# BackplaneConnector.net
KiCad netlist of a schematic drawn in Altium Designer
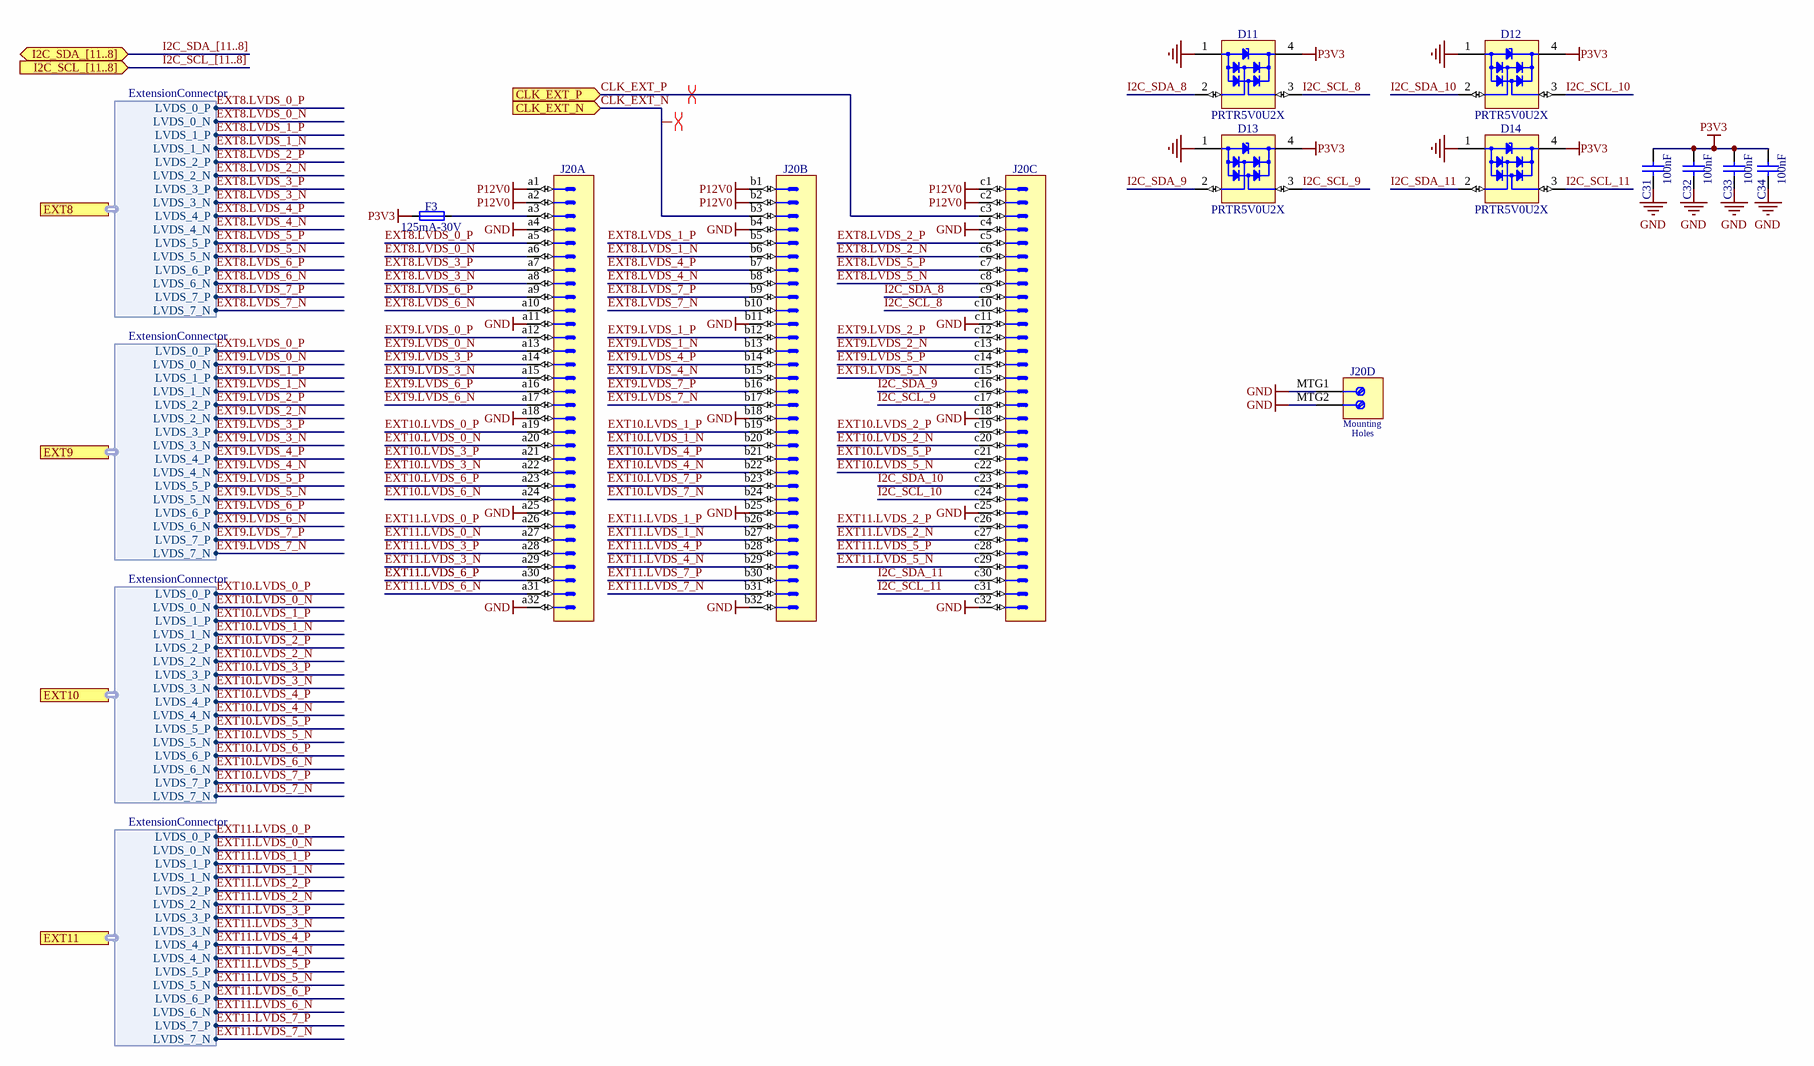
[diagram p0: BackplaneConnector.SchDoc]

(export (version "E")
  (design (tool "Eeschema 10.0.6"))
  (components
    (comp (ref "C31")
      (value "100nF")
      (footprint "CAPC0603X33N")
      (description "Non-polarised capacitor")
      (fields
        (field (name "PART NUMBER") "CC0201_100NF_6.3V_10%_X5R")
        (field (name "VOLTAGE") "6.3V")
        (field (name "AUTHOR") "CERN DEM JLC")
      )
      (libsource (lib "Capacitors") (part "Capacitor - non polarized"))
    )
    (comp (ref "C32")
      (value "100nF")
      (footprint "CAPC0603X33N")
      (description "Non-polarised capacitor")
      (fields
        (field (name "PART NUMBER") "CC0201_100NF_6.3V_10%_X5R")
        (field (name "VOLTAGE") "6.3V")
        (field (name "AUTHOR") "CERN DEM JLC")
      )
      (libsource (lib "Capacitors") (part "Capacitor - non polarized"))
    )
    (comp (ref "C33")
      (value "100nF")
      (footprint "CAPC0603X33N")
      (description "Non-polarised capacitor")
      (fields
        (field (name "PART NUMBER") "CC0201_100NF_6.3V_10%_X5R")
        (field (name "VOLTAGE") "6.3V")
        (field (name "AUTHOR") "CERN DEM JLC")
      )
      (libsource (lib "Capacitors") (part "Capacitor - non polarized"))
    )
    (comp (ref "C34")
      (value "100nF")
      (footprint "CAPC0603X33N")
      (description "Non-polarised capacitor")
      (fields
        (field (name "PART NUMBER") "CC0201_100NF_6.3V_10%_X5R")
        (field (name "VOLTAGE") "6.3V")
        (field (name "AUTHOR") "CERN DEM JLC")
      )
      (libsource (lib "Capacitors") (part "Capacitor - non polarized"))
    )
    (comp (ref "D11")
      (value "PRTR5V0U2X")
      (footprint "SOT190P230X110-4N")
      (description "Ultra Low Capacitance Double Rail-to-Rail ESD Protection Diode")
      (fields
        (field (name "VOLTAGE") "5.5V")
        (field (name "MANUFACTURER") "NXP SEMICONDUCTORS")
        (field (name "AUTHOR") "CERN DEM JLC")
      )
      (libsource (lib "ICs And Semiconductors") (part "PRTR5V0U2X"))
    )
    (comp (ref "D12")
      (value "PRTR5V0U2X")
      (footprint "SOT190P230X110-4N")
      (description "Ultra Low Capacitance Double Rail-to-Rail ESD Protection Diode")
      (fields
        (field (name "VOLTAGE") "5.5V")
        (field (name "MANUFACTURER") "NXP SEMICONDUCTORS")
        (field (name "AUTHOR") "CERN DEM JLC")
      )
      (libsource (lib "ICs And Semiconductors") (part "PRTR5V0U2X"))
    )
    (comp (ref "D13")
      (value "PRTR5V0U2X")
      (footprint "SOT190P230X110-4N")
      (description "Ultra Low Capacitance Double Rail-to-Rail ESD Protection Diode")
      (fields
        (field (name "VOLTAGE") "5.5V")
        (field (name "MANUFACTURER") "NXP SEMICONDUCTORS")
        (field (name "AUTHOR") "CERN DEM JLC")
      )
      (libsource (lib "ICs And Semiconductors") (part "PRTR5V0U2X"))
    )
    (comp (ref "D14")
      (value "PRTR5V0U2X")
      (footprint "SOT190P230X110-4N")
      (description "Ultra Low Capacitance Double Rail-to-Rail ESD Protection Diode")
      (fields
        (field (name "VOLTAGE") "5.5V")
        (field (name "MANUFACTURER") "NXP SEMICONDUCTORS")
        (field (name "AUTHOR") "CERN DEM JLC")
      )
      (libsource (lib "ICs And Semiconductors") (part "PRTR5V0U2X"))
    )
    (comp (ref "F3")
      (value "125mA-30V")
      (footprint "FUSR_LITTELFUSE_1206L012")
      (description "Fuse")
      (fields
        (field (name "PART NUMBER") "FUSR_LITTELFUSE_1206L012")
        (field (name "MANUFACTURER") "LITTELFUSE")
        (field (name "AUTHOR") "CERN DEM JLC")
      )
      (libsource (lib "Eletro-mechanical") (part "Fuse"))
    )
    (comp (ref "J20")
      (value "DIN 41612 Type C")
      (footprint "HARTING_09 03 196 2921")
      (description "Connector 96abc male (3x32)")
      (fields
        (field (name "PART NUMBER") "HARTING_09 03 196 2921")
        (field (name "MANUFACTURER") "HARTING")
        (field (name "AUTHOR") "CERN DEM JLC")
      )
      (libsource (lib "Connectors") (part "Connector 96abc male (3x32)"))
    )
  )
  (nets
    (net (code "2") (name "/CLK_EXT_N") (class "Default")
      (node (ref "J20") (pin "b3") (pinfunction "b3_b3") (pintype "bidirectional"))
    )
    (net (code "3") (name "/CLK_EXT_P") (class "Default")
      (node (ref "J20") (pin "c3") (pinfunction "c3_c3") (pintype "bidirectional"))
    )
    (net (code "4") (name "/EXT8.LVDS_0_N") (class "Default")
      (node (ref "J20") (pin "a6") (pinfunction "a6_a6") (pintype "bidirectional"))
    )
    (net (code "5") (name "/EXT8.LVDS_0_P") (class "Default")
      (node (ref "J20") (pin "a5") (pinfunction "a5_a5") (pintype "bidirectional"))
    )
    (net (code "6") (name "/EXT8.LVDS_1_N") (class "Default")
      (node (ref "J20") (pin "b6") (pinfunction "b6_b6") (pintype "bidirectional"))
    )
    (net (code "7") (name "/EXT8.LVDS_1_P") (class "Default")
      (node (ref "J20") (pin "b5") (pinfunction "b5_b5") (pintype "bidirectional"))
    )
    (net (code "8") (name "/EXT8.LVDS_2_N") (class "Default")
      (node (ref "J20") (pin "c6") (pinfunction "c6_c6") (pintype "bidirectional"))
    )
    (net (code "9") (name "/EXT8.LVDS_2_P") (class "Default")
      (node (ref "J20") (pin "c5") (pinfunction "c5_c5") (pintype "bidirectional"))
    )
    (net (code "10") (name "/EXT8.LVDS_3_N") (class "Default")
      (node (ref "J20") (pin "a8") (pinfunction "a8_a8") (pintype "bidirectional"))
    )
    (net (code "11") (name "/EXT8.LVDS_3_P") (class "Default")
      (node (ref "J20") (pin "a7") (pinfunction "a7_a7") (pintype "bidirectional"))
    )
    (net (code "12") (name "/EXT8.LVDS_4_N") (class "Default")
      (node (ref "J20") (pin "b8") (pinfunction "b8_b8") (pintype "bidirectional"))
    )
    (net (code "13") (name "/EXT8.LVDS_4_P") (class "Default")
      (node (ref "J20") (pin "b7") (pinfunction "b7_b7") (pintype "bidirectional"))
    )
    (net (code "14") (name "/EXT8.LVDS_5_N") (class "Default")
      (node (ref "J20") (pin "c8") (pinfunction "c8_c8") (pintype "bidirectional"))
    )
    (net (code "15") (name "/EXT8.LVDS_5_P") (class "Default")
      (node (ref "J20") (pin "c7") (pinfunction "c7_c7") (pintype "bidirectional"))
    )
    (net (code "16") (name "/EXT8.LVDS_6_N") (class "Default")
      (node (ref "J20") (pin "a10") (pinfunction "a10_a10") (pintype "bidirectional"))
    )
    (net (code "17") (name "/EXT8.LVDS_6_P") (class "Default")
      (node (ref "J20") (pin "a9") (pinfunction "a9_a9") (pintype "bidirectional"))
    )
    (net (code "18") (name "/EXT8.LVDS_7_N") (class "Default")
      (node (ref "J20") (pin "b10") (pinfunction "b10_b10") (pintype "bidirectional"))
    )
    (net (code "19") (name "/EXT8.LVDS_7_P") (class "Default")
      (node (ref "J20") (pin "b9") (pinfunction "b9_b9") (pintype "bidirectional"))
    )
    (net (code "20") (name "/EXT9.LVDS_0_N") (class "Default")
      (node (ref "J20") (pin "a13") (pinfunction "a13_a13") (pintype "bidirectional"))
    )
    (net (code "21") (name "/EXT9.LVDS_0_P") (class "Default")
      (node (ref "J20") (pin "a12") (pinfunction "a12_a12") (pintype "bidirectional"))
    )
    (net (code "22") (name "/EXT9.LVDS_1_N") (class "Default")
      (node (ref "J20") (pin "b13") (pinfunction "b13_b13") (pintype "bidirectional"))
    )
    (net (code "23") (name "/EXT9.LVDS_1_P") (class "Default")
      (node (ref "J20") (pin "b12") (pinfunction "b12_b12") (pintype "bidirectional"))
    )
    (net (code "24") (name "/EXT9.LVDS_2_N") (class "Default")
      (node (ref "J20") (pin "c13") (pinfunction "c13_c13") (pintype "bidirectional"))
    )
    (net (code "25") (name "/EXT9.LVDS_2_P") (class "Default")
      (node (ref "J20") (pin "c12") (pinfunction "c12_c12") (pintype "bidirectional"))
    )
    (net (code "26") (name "/EXT9.LVDS_3_N") (class "Default")
      (node (ref "J20") (pin "a15") (pinfunction "a15_a15") (pintype "bidirectional"))
    )
    (net (code "27") (name "/EXT9.LVDS_3_P") (class "Default")
      (node (ref "J20") (pin "a14") (pinfunction "a14_a14") (pintype "bidirectional"))
    )
    (net (code "28") (name "/EXT9.LVDS_4_N") (class "Default")
      (node (ref "J20") (pin "b15") (pinfunction "b15_b15") (pintype "bidirectional"))
    )
    (net (code "29") (name "/EXT9.LVDS_4_P") (class "Default")
      (node (ref "J20") (pin "b14") (pinfunction "b14_b14") (pintype "bidirectional"))
    )
    (net (code "30") (name "/EXT9.LVDS_5_N") (class "Default")
      (node (ref "J20") (pin "c15") (pinfunction "c15_c15") (pintype "bidirectional"))
    )
    (net (code "31") (name "/EXT9.LVDS_5_P") (class "Default")
      (node (ref "J20") (pin "c14") (pinfunction "c14_c14") (pintype "bidirectional"))
    )
    (net (code "32") (name "/EXT9.LVDS_6_N") (class "Default")
      (node (ref "J20") (pin "a17") (pinfunction "a17_a17") (pintype "bidirectional"))
    )
    (net (code "33") (name "/EXT9.LVDS_6_P") (class "Default")
      (node (ref "J20") (pin "a16") (pinfunction "a16_a16") (pintype "bidirectional"))
    )
    (net (code "34") (name "/EXT9.LVDS_7_N") (class "Default")
      (node (ref "J20") (pin "b17") (pinfunction "b17_b17") (pintype "bidirectional"))
    )
    (net (code "35") (name "/EXT9.LVDS_7_P") (class "Default")
      (node (ref "J20") (pin "b16") (pinfunction "b16_b16") (pintype "bidirectional"))
    )
    (net (code "36") (name "/EXT10.LVDS_0_N") (class "Default")
      (node (ref "J20") (pin "a20") (pinfunction "a20_a20") (pintype "bidirectional"))
    )
    (net (code "37") (name "/EXT10.LVDS_0_P") (class "Default")
      (node (ref "J20") (pin "a19") (pinfunction "a19_a19") (pintype "bidirectional"))
    )
    (net (code "38") (name "/EXT10.LVDS_1_N") (class "Default")
      (node (ref "J20") (pin "b20") (pinfunction "b20_b20") (pintype "bidirectional"))
    )
    (net (code "39") (name "/EXT10.LVDS_1_P") (class "Default")
      (node (ref "J20") (pin "b19") (pinfunction "b19_b19") (pintype "bidirectional"))
    )
    (net (code "40") (name "/EXT10.LVDS_2_N") (class "Default")
      (node (ref "J20") (pin "c20") (pinfunction "c20_c20") (pintype "bidirectional"))
    )
    (net (code "41") (name "/EXT10.LVDS_2_P") (class "Default")
      (node (ref "J20") (pin "c19") (pinfunction "c19_c19") (pintype "bidirectional"))
    )
    (net (code "42") (name "/EXT10.LVDS_3_N") (class "Default")
      (node (ref "J20") (pin "a22") (pinfunction "a22_a22") (pintype "bidirectional"))
    )
    (net (code "43") (name "/EXT10.LVDS_3_P") (class "Default")
      (node (ref "J20") (pin "a21") (pinfunction "a21_a21") (pintype "bidirectional"))
    )
    (net (code "44") (name "/EXT10.LVDS_4_N") (class "Default")
      (node (ref "J20") (pin "b22") (pinfunction "b22_b22") (pintype "bidirectional"))
    )
    (net (code "45") (name "/EXT10.LVDS_4_P") (class "Default")
      (node (ref "J20") (pin "b21") (pinfunction "b21_b21") (pintype "bidirectional"))
    )
    (net (code "46") (name "/EXT10.LVDS_5_N") (class "Default")
      (node (ref "J20") (pin "c22") (pinfunction "c22_c22") (pintype "bidirectional"))
    )
    (net (code "47") (name "/EXT10.LVDS_5_P") (class "Default")
      (node (ref "J20") (pin "c21") (pinfunction "c21_c21") (pintype "bidirectional"))
    )
    (net (code "48") (name "/EXT10.LVDS_6_N") (class "Default")
      (node (ref "J20") (pin "a24") (pinfunction "a24_a24") (pintype "bidirectional"))
    )
    (net (code "49") (name "/EXT10.LVDS_6_P") (class "Default")
      (node (ref "J20") (pin "a23") (pinfunction "a23_a23") (pintype "bidirectional"))
    )
    (net (code "50") (name "/EXT10.LVDS_7_N") (class "Default")
      (node (ref "J20") (pin "b24") (pinfunction "b24_b24") (pintype "bidirectional"))
    )
    (net (code "51") (name "/EXT10.LVDS_7_P") (class "Default")
      (node (ref "J20") (pin "b23") (pinfunction "b23_b23") (pintype "bidirectional"))
    )
    (net (code "52") (name "/EXT11.LVDS_0_N") (class "Default")
      (node (ref "J20") (pin "a27") (pinfunction "a27_a27") (pintype "bidirectional"))
    )
    (net (code "53") (name "/EXT11.LVDS_0_P") (class "Default")
      (node (ref "J20") (pin "a26") (pinfunction "a26_a26") (pintype "bidirectional"))
    )
    (net (code "54") (name "/EXT11.LVDS_1_N") (class "Default")
      (node (ref "J20") (pin "b27") (pinfunction "b27_b27") (pintype "bidirectional"))
    )
    (net (code "55") (name "/EXT11.LVDS_1_P") (class "Default")
      (node (ref "J20") (pin "b26") (pinfunction "b26_b26") (pintype "bidirectional"))
    )
    (net (code "56") (name "/EXT11.LVDS_2_N") (class "Default")
      (node (ref "J20") (pin "c27") (pinfunction "c27_c27") (pintype "bidirectional"))
    )
    (net (code "57") (name "/EXT11.LVDS_2_P") (class "Default")
      (node (ref "J20") (pin "c26") (pinfunction "c26_c26") (pintype "bidirectional"))
    )
    (net (code "58") (name "/EXT11.LVDS_3_N") (class "Default")
      (node (ref "J20") (pin "a29") (pinfunction "a29_a29") (pintype "bidirectional"))
    )
    (net (code "59") (name "/EXT11.LVDS_3_P") (class "Default")
      (node (ref "J20") (pin "a28") (pinfunction "a28_a28") (pintype "bidirectional"))
    )
    (net (code "60") (name "/EXT11.LVDS_4_N") (class "Default")
      (node (ref "J20") (pin "b29") (pinfunction "b29_b29") (pintype "bidirectional"))
    )
    (net (code "61") (name "/EXT11.LVDS_4_P") (class "Default")
      (node (ref "J20") (pin "b28") (pinfunction "b28_b28") (pintype "bidirectional"))
    )
    (net (code "62") (name "/EXT11.LVDS_5_N") (class "Default")
      (node (ref "J20") (pin "c29") (pinfunction "c29_c29") (pintype "bidirectional"))
    )
    (net (code "63") (name "/EXT11.LVDS_5_P") (class "Default")
      (node (ref "J20") (pin "c28") (pinfunction "c28_c28") (pintype "bidirectional"))
    )
    (net (code "64") (name "/EXT11.LVDS_6_N") (class "Default")
      (node (ref "J20") (pin "a31") (pinfunction "a31_a31") (pintype "bidirectional"))
    )
    (net (code "65") (name "/EXT11.LVDS_6_P") (class "Default")
      (node (ref "J20") (pin "a30") (pinfunction "a30_a30") (pintype "bidirectional"))
    )
    (net (code "66") (name "/EXT11.LVDS_7_N") (class "Default")
      (node (ref "J20") (pin "b31") (pinfunction "b31_b31") (pintype "bidirectional"))
    )
    (net (code "67") (name "/EXT11.LVDS_7_P") (class "Default")
      (node (ref "J20") (pin "b30") (pinfunction "b30_b30") (pintype "bidirectional"))
    )
    (net (code "68") (name "/I2C_SCL_8") (class "Default")
      (node (ref "D11") (pin "3") (pinfunction "I/O2_3") (pintype "bidirectional"))
      (node (ref "J20") (pin "c10") (pinfunction "c10_c10") (pintype "bidirectional"))
    )
    (net (code "69") (name "/I2C_SCL_9") (class "Default")
      (node (ref "D13") (pin "3") (pinfunction "I/O2_3") (pintype "bidirectional"))
      (node (ref "J20") (pin "c17") (pinfunction "c17_c17") (pintype "bidirectional"))
    )
    (net (code "70") (name "/I2C_SCL_10") (class "Default")
      (node (ref "D12") (pin "3") (pinfunction "I/O2_3") (pintype "bidirectional"))
      (node (ref "J20") (pin "c24") (pinfunction "c24_c24") (pintype "bidirectional"))
    )
    (net (code "71") (name "/I2C_SCL_11") (class "Default")
      (node (ref "D14") (pin "3") (pinfunction "I/O2_3") (pintype "bidirectional"))
      (node (ref "J20") (pin "c31") (pinfunction "c31_c31") (pintype "bidirectional"))
    )
    (net (code "73") (name "/I2C_SDA_8") (class "Default")
      (node (ref "D11") (pin "2") (pinfunction "I/O1_2") (pintype "bidirectional"))
      (node (ref "J20") (pin "c9") (pinfunction "c9_c9") (pintype "bidirectional"))
    )
    (net (code "74") (name "/I2C_SDA_9") (class "Default")
      (node (ref "D13") (pin "2") (pinfunction "I/O1_2") (pintype "bidirectional"))
      (node (ref "J20") (pin "c16") (pinfunction "c16_c16") (pintype "bidirectional"))
    )
    (net (code "75") (name "/I2C_SDA_10") (class "Default")
      (node (ref "D12") (pin "2") (pinfunction "I/O1_2") (pintype "bidirectional"))
      (node (ref "J20") (pin "c23") (pinfunction "c23_c23") (pintype "bidirectional"))
    )
    (net (code "76") (name "/I2C_SDA_11") (class "Default")
      (node (ref "D14") (pin "2") (pinfunction "I/O1_2") (pintype "bidirectional"))
      (node (ref "J20") (pin "c30") (pinfunction "c30_c30") (pintype "bidirectional"))
    )
    (net (code "79") (name "GND") (class "Default")
      (node (ref "C31") (pin "1") (pinfunction "1_1") (pintype "passive"))
      (node (ref "C32") (pin "1") (pinfunction "1_1") (pintype "passive"))
      (node (ref "C33") (pin "1") (pinfunction "1_1") (pintype "passive"))
      (node (ref "C34") (pin "1") (pinfunction "1_1") (pintype "passive"))
      (node (ref "D11") (pin "1") (pinfunction "GND_1") (pintype "power_in"))
      (node (ref "D12") (pin "1") (pinfunction "GND_1") (pintype "power_in"))
      (node (ref "D13") (pin "1") (pinfunction "GND_1") (pintype "power_in"))
      (node (ref "D14") (pin "1") (pinfunction "GND_1") (pintype "power_in"))
      (node (ref "J20") (pin "MTG1") (pinfunction "MTG1_MTG1") (pintype "passive"))
      (node (ref "J20") (pin "MTG2") (pinfunction "MTG2_MTG2") (pintype "passive"))
      (node (ref "J20") (pin "a11") (pinfunction "a11_a11") (pintype "bidirectional"))
      (node (ref "J20") (pin "a18") (pinfunction "a18_a18") (pintype "bidirectional"))
      (node (ref "J20") (pin "a25") (pinfunction "a25_a25") (pintype "bidirectional"))
      (node (ref "J20") (pin "a32") (pinfunction "a32_a32") (pintype "bidirectional"))
      (node (ref "J20") (pin "a4") (pinfunction "a4_a4") (pintype "bidirectional"))
      (node (ref "J20") (pin "b11") (pinfunction "b11_b11") (pintype "bidirectional"))
      (node (ref "J20") (pin "b18") (pinfunction "b18_b18") (pintype "bidirectional"))
      (node (ref "J20") (pin "b25") (pinfunction "b25_b25") (pintype "bidirectional"))
      (node (ref "J20") (pin "b32") (pinfunction "b32_b32") (pintype "bidirectional"))
      (node (ref "J20") (pin "b4") (pinfunction "b4_b4") (pintype "bidirectional"))
      (node (ref "J20") (pin "c11") (pinfunction "c11_c11") (pintype "bidirectional"))
      (node (ref "J20") (pin "c18") (pinfunction "c18_c18") (pintype "bidirectional"))
      (node (ref "J20") (pin "c25") (pinfunction "c25_c25") (pintype "bidirectional"))
      (node (ref "J20") (pin "c32") (pinfunction "c32_c32") (pintype "bidirectional"))
      (node (ref "J20") (pin "c4") (pinfunction "c4_c4") (pintype "bidirectional"))
    )
    (net (code "80") (name "Net-(F3-Pad2)") (class "Default")
      (node (ref "F3") (pin "2") (pinfunction "2_2") (pintype "passive"))
      (node (ref "J20") (pin "a3") (pinfunction "a3_a3") (pintype "bidirectional"))
    )
    (net (code "81") (name "P3V3") (class "Default")
      (node (ref "C31") (pin "2") (pinfunction "2_2") (pintype "passive"))
      (node (ref "C32") (pin "2") (pinfunction "2_2") (pintype "passive"))
      (node (ref "C33") (pin "2") (pinfunction "2_2") (pintype "passive"))
      (node (ref "C34") (pin "2") (pinfunction "2_2") (pintype "passive"))
      (node (ref "D11") (pin "4") (pinfunction "VCC_4") (pintype "power_in"))
      (node (ref "D12") (pin "4") (pinfunction "VCC_4") (pintype "power_in"))
      (node (ref "D13") (pin "4") (pinfunction "VCC_4") (pintype "power_in"))
      (node (ref "D14") (pin "4") (pinfunction "VCC_4") (pintype "power_in"))
      (node (ref "F3") (pin "1") (pinfunction "1_1") (pintype "passive"))
    )
    (net (code "82") (name "P12V0") (class "Default")
      (node (ref "J20") (pin "a1") (pinfunction "a1_a1") (pintype "bidirectional"))
      (node (ref "J20") (pin "a2") (pinfunction "a2_a2") (pintype "bidirectional"))
      (node (ref "J20") (pin "b1") (pinfunction "b1_b1") (pintype "bidirectional"))
      (node (ref "J20") (pin "b2") (pinfunction "b2_b2") (pintype "bidirectional"))
      (node (ref "J20") (pin "c1") (pinfunction "c1_c1") (pintype "bidirectional"))
      (node (ref "J20") (pin "c2") (pinfunction "c2_c2") (pintype "bidirectional"))
    )
  )
)
